# R302X.net
KiCad netlist of a schematic drawn in EAGLE
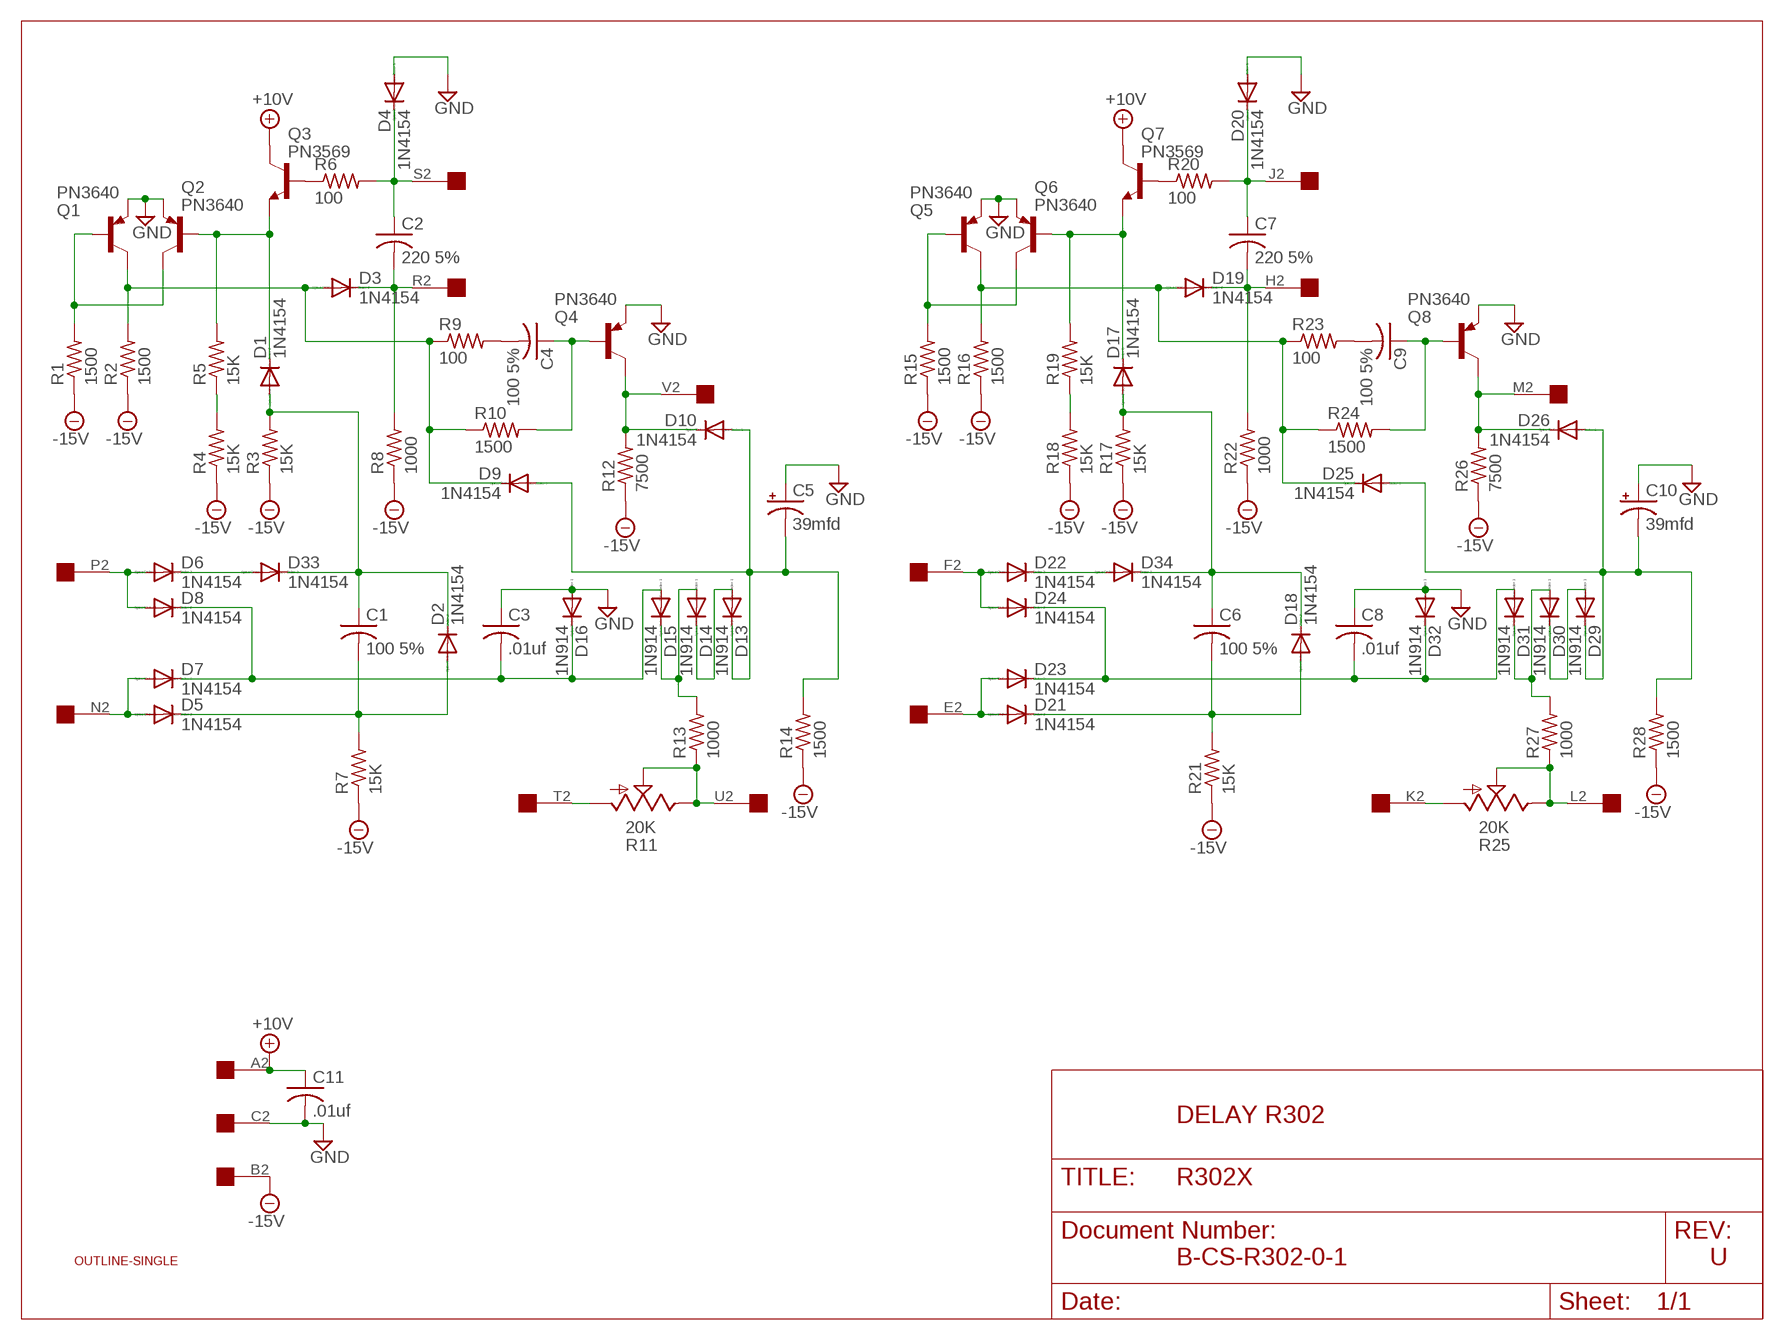
[diagram p0: schematic, sheet 1]

(export (version "E")
  (design (tool "Eeschema 10.0.6"))
  (components
    (comp (ref "C1")
      (value "100 5%")
      (footprint "eagle-import:C050-025X075")
      (libsource (lib "eagle-import") (part "C-US050-025X075"))
    )
    (comp (ref "C2")
      (value "220 5%")
      (footprint "eagle-import:C050-025X075")
      (libsource (lib "eagle-import") (part "C-US050-025X075"))
    )
    (comp (ref "C3")
      (value ".01uf")
      (footprint "eagle-import:C050-025X075")
      (libsource (lib "eagle-import") (part "C-US050-025X075"))
    )
    (comp (ref "C4")
      (value "100 5%")
      (footprint "eagle-import:C050-025X075")
      (libsource (lib "eagle-import") (part "C-US050-025X075"))
    )
    (comp (ref "C5")
      (value "39mfd")
      (footprint "eagle-import:E15-5")
      (libsource (lib "eagle-import") (part "CPOL-USE15-5AXIAL"))
    )
    (comp (ref "C6")
      (value "100 5%")
      (footprint "eagle-import:C050-025X075")
      (libsource (lib "eagle-import") (part "C-US050-025X075"))
    )
    (comp (ref "C7")
      (value "220 5%")
      (footprint "eagle-import:C050-025X075")
      (libsource (lib "eagle-import") (part "C-US050-025X075"))
    )
    (comp (ref "C8")
      (value ".01uf")
      (footprint "eagle-import:C050-025X075")
      (libsource (lib "eagle-import") (part "C-US050-025X075"))
    )
    (comp (ref "C9")
      (value "100 5%")
      (footprint "eagle-import:C050-025X075")
      (libsource (lib "eagle-import") (part "C-US050-025X075"))
    )
    (comp (ref "C10")
      (value "39mfd")
      (footprint "eagle-import:E15-5")
      (libsource (lib "eagle-import") (part "CPOL-USE15-5AXIAL"))
    )
    (comp (ref "C11")
      (value ".01uf")
      (footprint "eagle-import:C050-025X075")
      (libsource (lib "eagle-import") (part "C-US050-025X075"))
    )
    (comp (ref "D1")
      (value "1N4154")
      (footprint "eagle-import:DO35-10")
      (libsource (lib "eagle-import") (part "1N4148DO35-10"))
    )
    (comp (ref "D2")
      (value "1N4154")
      (footprint "eagle-import:DO35-10")
      (libsource (lib "eagle-import") (part "1N4148DO35-10"))
    )
    (comp (ref "D3")
      (value "1N4154")
      (footprint "eagle-import:DO35-10")
      (libsource (lib "eagle-import") (part "1N4148DO35-10"))
    )
    (comp (ref "D4")
      (value "1N4154")
      (footprint "eagle-import:DO35-10")
      (libsource (lib "eagle-import") (part "1N4148DO35-10"))
    )
    (comp (ref "D5")
      (value "1N4154")
      (footprint "eagle-import:DO35-10")
      (libsource (lib "eagle-import") (part "1N4148DO35-10"))
    )
    (comp (ref "D6")
      (value "1N4154")
      (footprint "eagle-import:DO35-10")
      (libsource (lib "eagle-import") (part "1N4148DO35-10"))
    )
    (comp (ref "D7")
      (value "1N4154")
      (footprint "eagle-import:DO35-10")
      (libsource (lib "eagle-import") (part "1N4148DO35-10"))
    )
    (comp (ref "D8")
      (value "1N4154")
      (footprint "eagle-import:DO35-10")
      (libsource (lib "eagle-import") (part "1N4148DO35-10"))
    )
    (comp (ref "D9")
      (value "1N4154")
      (footprint "eagle-import:DO35-10")
      (libsource (lib "eagle-import") (part "1N4148DO35-10"))
    )
    (comp (ref "D10")
      (value "1N4154")
      (footprint "eagle-import:DO35-10")
      (libsource (lib "eagle-import") (part "1N4148DO35-10"))
    )
    (comp (ref "D13")
      (value "1N914")
      (footprint "eagle-import:DO35-10")
      (libsource (lib "eagle-import") (part "1N4148DO35-10"))
    )
    (comp (ref "D14")
      (value "1N914")
      (footprint "eagle-import:DO35-10")
      (libsource (lib "eagle-import") (part "1N4148DO35-10"))
    )
    (comp (ref "D15")
      (value "1N914")
      (footprint "eagle-import:DO35-10")
      (libsource (lib "eagle-import") (part "1N4148DO35-10"))
    )
    (comp (ref "D16")
      (value "1N914")
      (footprint "eagle-import:DO35-10")
      (libsource (lib "eagle-import") (part "1N4148DO35-10"))
    )
    (comp (ref "D17")
      (value "1N4154")
      (footprint "eagle-import:DO35-10")
      (libsource (lib "eagle-import") (part "1N4148DO35-10"))
    )
    (comp (ref "D18")
      (value "1N4154")
      (footprint "eagle-import:DO35-10")
      (libsource (lib "eagle-import") (part "1N4148DO35-10"))
    )
    (comp (ref "D19")
      (value "1N4154")
      (footprint "eagle-import:DO35-10")
      (libsource (lib "eagle-import") (part "1N4148DO35-10"))
    )
    (comp (ref "D20")
      (value "1N4154")
      (footprint "eagle-import:DO35-10")
      (libsource (lib "eagle-import") (part "1N4148DO35-10"))
    )
    (comp (ref "D21")
      (value "1N4154")
      (footprint "eagle-import:DO35-10")
      (libsource (lib "eagle-import") (part "1N4148DO35-10"))
    )
    (comp (ref "D22")
      (value "1N4154")
      (footprint "eagle-import:DO35-10")
      (libsource (lib "eagle-import") (part "1N4148DO35-10"))
    )
    (comp (ref "D23")
      (value "1N4154")
      (footprint "eagle-import:DO35-10")
      (libsource (lib "eagle-import") (part "1N4148DO35-10"))
    )
    (comp (ref "D24")
      (value "1N4154")
      (footprint "eagle-import:DO35-10")
      (libsource (lib "eagle-import") (part "1N4148DO35-10"))
    )
    (comp (ref "D25")
      (value "1N4154")
      (footprint "eagle-import:DO35-10")
      (libsource (lib "eagle-import") (part "1N4148DO35-10"))
    )
    (comp (ref "D26")
      (value "1N4154")
      (footprint "eagle-import:DO35-10")
      (libsource (lib "eagle-import") (part "1N4148DO35-10"))
    )
    (comp (ref "D29")
      (value "1N914")
      (footprint "eagle-import:DO35-10")
      (libsource (lib "eagle-import") (part "1N4148DO35-10"))
    )
    (comp (ref "D30")
      (value "1N914")
      (footprint "eagle-import:DO35-10")
      (libsource (lib "eagle-import") (part "1N4148DO35-10"))
    )
    (comp (ref "D31")
      (value "1N914")
      (footprint "eagle-import:DO35-10")
      (libsource (lib "eagle-import") (part "1N4148DO35-10"))
    )
    (comp (ref "D32")
      (value "1N914")
      (footprint "eagle-import:DO35-10")
      (libsource (lib "eagle-import") (part "1N4148DO35-10"))
    )
    (comp (ref "D33")
      (value "1N4154")
      (footprint "eagle-import:DO35-10")
      (libsource (lib "eagle-import") (part "1N4148DO35-10"))
    )
    (comp (ref "D34")
      (value "1N4154")
      (footprint "eagle-import:DO35-10")
      (libsource (lib "eagle-import") (part "1N4148DO35-10"))
    )
    (comp (ref "Q1")
      (value "PN3640")
      (footprint "eagle-import:TO39")
      (libsource (lib "eagle-import") (part "2N3637"))
    )
    (comp (ref "Q2")
      (value "PN3640")
      (footprint "eagle-import:TO39")
      (libsource (lib "eagle-import") (part "2N3637"))
    )
    (comp (ref "Q3")
      (value "PN3569")
      (footprint "eagle-import:TO39")
      (libsource (lib "eagle-import") (part "-NPN-TO39-EBC2N3019"))
    )
    (comp (ref "Q4")
      (value "PN3640")
      (footprint "eagle-import:TO39")
      (libsource (lib "eagle-import") (part "2N3637"))
    )
    (comp (ref "Q5")
      (value "PN3640")
      (footprint "eagle-import:TO39")
      (libsource (lib "eagle-import") (part "2N3637"))
    )
    (comp (ref "Q6")
      (value "PN3640")
      (footprint "eagle-import:TO39")
      (libsource (lib "eagle-import") (part "2N3637"))
    )
    (comp (ref "Q7")
      (value "PN3569")
      (footprint "eagle-import:TO39")
      (libsource (lib "eagle-import") (part "-NPN-TO39-EBC2N3019"))
    )
    (comp (ref "Q8")
      (value "PN3640")
      (footprint "eagle-import:TO39")
      (libsource (lib "eagle-import") (part "2N3637"))
    )
    (comp (ref "R1")
      (value "1500")
      (footprint "eagle-import:0207_10")
      (libsource (lib "eagle-import") (part "R-US_0207/10"))
    )
    (comp (ref "R2")
      (value "1500")
      (footprint "eagle-import:0207_10")
      (libsource (lib "eagle-import") (part "R-US_0207/10"))
    )
    (comp (ref "R3")
      (value "15K")
      (footprint "eagle-import:0207_10")
      (libsource (lib "eagle-import") (part "R-US_0207/10"))
    )
    (comp (ref "R4")
      (value "15K")
      (footprint "eagle-import:0207_10")
      (libsource (lib "eagle-import") (part "R-US_0207/10"))
    )
    (comp (ref "R5")
      (value "15K")
      (footprint "eagle-import:0207_10")
      (libsource (lib "eagle-import") (part "R-US_0207/10"))
    )
    (comp (ref "R6")
      (value "100")
      (footprint "eagle-import:0207_10")
      (libsource (lib "eagle-import") (part "R-US_0207/10"))
    )
    (comp (ref "R7")
      (value "15K")
      (footprint "eagle-import:0207_10")
      (libsource (lib "eagle-import") (part "R-US_0207/10"))
    )
    (comp (ref "R8")
      (value "1000")
      (footprint "eagle-import:0207_10")
      (libsource (lib "eagle-import") (part "R-US_0207/10"))
    )
    (comp (ref "R9")
      (value "100")
      (footprint "eagle-import:0207_10")
      (libsource (lib "eagle-import") (part "R-US_0207/10"))
    )
    (comp (ref "R10")
      (value "1500")
      (footprint "eagle-import:0207_10")
      (libsource (lib "eagle-import") (part "R-US_0207/10"))
    )
    (comp (ref "R11")
      (value "20K")
      (footprint "eagle-import:SP19L")
      (libsource (lib "eagle-import") (part "TRIM_US-S43P"))
    )
    (comp (ref "R12")
      (value "7500")
      (footprint "eagle-import:0207_10")
      (libsource (lib "eagle-import") (part "R-US_0207/10"))
    )
    (comp (ref "R13")
      (value "1000")
      (footprint "eagle-import:0207_10")
      (libsource (lib "eagle-import") (part "R-US_0207/10"))
    )
    (comp (ref "R14")
      (value "1500")
      (footprint "eagle-import:0207_10")
      (libsource (lib "eagle-import") (part "R-US_0207/10"))
    )
    (comp (ref "R15")
      (value "1500")
      (footprint "eagle-import:0207_10")
      (libsource (lib "eagle-import") (part "R-US_0207/10"))
    )
    (comp (ref "R16")
      (value "1500")
      (footprint "eagle-import:0207_10")
      (libsource (lib "eagle-import") (part "R-US_0207/10"))
    )
    (comp (ref "R17")
      (value "15K")
      (footprint "eagle-import:0207_10")
      (libsource (lib "eagle-import") (part "R-US_0207/10"))
    )
    (comp (ref "R18")
      (value "15K")
      (footprint "eagle-import:0207_10")
      (libsource (lib "eagle-import") (part "R-US_0207/10"))
    )
    (comp (ref "R19")
      (value "15K")
      (footprint "eagle-import:0207_10")
      (libsource (lib "eagle-import") (part "R-US_0207/10"))
    )
    (comp (ref "R20")
      (value "100")
      (footprint "eagle-import:0207_10")
      (libsource (lib "eagle-import") (part "R-US_0207/10"))
    )
    (comp (ref "R21")
      (value "15K")
      (footprint "eagle-import:0207_10")
      (libsource (lib "eagle-import") (part "R-US_0207/10"))
    )
    (comp (ref "R22")
      (value "1000")
      (footprint "eagle-import:0207_10")
      (libsource (lib "eagle-import") (part "R-US_0207/10"))
    )
    (comp (ref "R23")
      (value "100")
      (footprint "eagle-import:0207_10")
      (libsource (lib "eagle-import") (part "R-US_0207/10"))
    )
    (comp (ref "R24")
      (value "1500")
      (footprint "eagle-import:0207_10")
      (libsource (lib "eagle-import") (part "R-US_0207/10"))
    )
    (comp (ref "R25")
      (value "20K")
      (footprint "eagle-import:SP19L")
      (libsource (lib "eagle-import") (part "TRIM_US-S43P"))
    )
    (comp (ref "R26")
      (value "7500")
      (footprint "eagle-import:0207_10")
      (libsource (lib "eagle-import") (part "R-US_0207/10"))
    )
    (comp (ref "R27")
      (value "1000")
      (footprint "eagle-import:0207_10")
      (libsource (lib "eagle-import") (part "R-US_0207/10"))
    )
    (comp (ref "R28")
      (value "1500")
      (footprint "eagle-import:0207_10")
      (libsource (lib "eagle-import") (part "R-US_0207/10"))
    )
    (comp (ref "U$1")
      (value "OUTLINE-SINGLE")
      (footprint "eagle-import:SINGLE")
      (libsource (lib "eagle-import") (part "OUTLINE-SINGLE"))
    )
    (comp (ref "U$2")
      (value "EDGE-1")
      (footprint "eagle-import:EDGE-CON1")
      (libsource (lib "eagle-import") (part "EDGE-1"))
    )
  )
  (nets
    (net (code "1") (name "+10V") (class "Default")
      (node (ref "C11") (pin "1") (pinfunction "1_1") (pintype "passive"))
      (node (ref "Q3") (pin "3") (pinfunction "C_3") (pintype "passive"))
      (node (ref "Q7") (pin "3") (pinfunction "C_3") (pintype "passive"))
      (node (ref "U$2") (pin "A2") (pinfunction "1_A2") (pintype "bidirectional"))
    )
    (net (code "2") (name "-15V") (class "Default")
      (node (ref "R1") (pin "1") (pinfunction "1_1") (pintype "passive"))
      (node (ref "R12") (pin "1") (pinfunction "1_1") (pintype "passive"))
      (node (ref "R14") (pin "1") (pinfunction "1_1") (pintype "passive"))
      (node (ref "R15") (pin "1") (pinfunction "1_1") (pintype "passive"))
      (node (ref "R16") (pin "1") (pinfunction "1_1") (pintype "passive"))
      (node (ref "R17") (pin "1") (pinfunction "1_1") (pintype "passive"))
      (node (ref "R18") (pin "1") (pinfunction "1_1") (pintype "passive"))
      (node (ref "R2") (pin "1") (pinfunction "1_1") (pintype "passive"))
      (node (ref "R21") (pin "1") (pinfunction "1_1") (pintype "passive"))
      (node (ref "R22") (pin "1") (pinfunction "1_1") (pintype "passive"))
      (node (ref "R26") (pin "1") (pinfunction "1_1") (pintype "passive"))
      (node (ref "R28") (pin "1") (pinfunction "1_1") (pintype "passive"))
      (node (ref "R3") (pin "1") (pinfunction "1_1") (pintype "passive"))
      (node (ref "R4") (pin "1") (pinfunction "1_1") (pintype "passive"))
      (node (ref "R7") (pin "1") (pinfunction "1_1") (pintype "passive"))
      (node (ref "R8") (pin "1") (pinfunction "1_1") (pintype "passive"))
      (node (ref "U$2") (pin "B2") (pinfunction "1_B2") (pintype "bidirectional"))
    )
    (net (code "3") (name "GND") (class "Default")
      (node (ref "C10") (pin "+") (pinfunction "+_+") (pintype "passive"))
      (node (ref "C11") (pin "2") (pinfunction "2_2") (pintype "passive"))
      (node (ref "C3") (pin "1") (pinfunction "1_1") (pintype "passive"))
      (node (ref "C5") (pin "+") (pinfunction "+_+") (pintype "passive"))
      (node (ref "C8") (pin "1") (pinfunction "1_1") (pintype "passive"))
      (node (ref "D16") (pin "A") (pinfunction "A_A") (pintype "passive"))
      (node (ref "D20") (pin "A") (pinfunction "A_A") (pintype "passive"))
      (node (ref "D32") (pin "A") (pinfunction "A_A") (pintype "passive"))
      (node (ref "D4") (pin "A") (pinfunction "A_A") (pintype "passive"))
      (node (ref "Q1") (pin "1") (pinfunction "E_1") (pintype "passive"))
      (node (ref "Q2") (pin "1") (pinfunction "E_1") (pintype "passive"))
      (node (ref "Q4") (pin "1") (pinfunction "E_1") (pintype "passive"))
      (node (ref "Q5") (pin "1") (pinfunction "E_1") (pintype "passive"))
      (node (ref "Q6") (pin "1") (pinfunction "E_1") (pintype "passive"))
      (node (ref "Q8") (pin "1") (pinfunction "E_1") (pintype "passive"))
      (node (ref "U$2") (pin "C2") (pinfunction "1_C2") (pintype "bidirectional"))
    )
    (net (code "4") (name "Net-(C1-Pad1)") (class "Default")
      (node (ref "C1") (pin "1") (pinfunction "1_1") (pintype "passive"))
      (node (ref "D1") (pin "A") (pinfunction "A_A") (pintype "passive"))
      (node (ref "D2") (pin "C") (pinfunction "C_C") (pintype "passive"))
      (node (ref "D33") (pin "C") (pinfunction "C_C") (pintype "passive"))
      (node (ref "R3") (pin "2") (pinfunction "2_2") (pintype "passive"))
    )
    (net (code "5") (name "Net-(C1-Pad2)") (class "Default")
      (node (ref "C1") (pin "2") (pinfunction "2_2") (pintype "passive"))
      (node (ref "D2") (pin "A") (pinfunction "A_A") (pintype "passive"))
      (node (ref "D5") (pin "C") (pinfunction "C_C") (pintype "passive"))
      (node (ref "R7") (pin "2") (pinfunction "2_2") (pintype "passive"))
    )
    (net (code "6") (name "Net-(C3-Pad2)") (class "Default")
      (node (ref "C3") (pin "2") (pinfunction "2_2") (pintype "passive"))
      (node (ref "D15") (pin "A") (pinfunction "A_A") (pintype "passive"))
      (node (ref "D16") (pin "C") (pinfunction "C_C") (pintype "passive"))
      (node (ref "D7") (pin "C") (pinfunction "C_C") (pintype "passive"))
      (node (ref "D8") (pin "C") (pinfunction "C_C") (pintype "passive"))
    )
    (net (code "7") (name "Net-(C4-Pad2)") (class "Default")
      (node (ref "C4") (pin "2") (pinfunction "2_2") (pintype "passive"))
      (node (ref "R9") (pin "2") (pinfunction "2_2") (pintype "passive"))
    )
    (net (code "8") (name "Net-(C5-Pad-)") (class "Default")
      (node (ref "C5") (pin "-") (pinfunction "-_-") (pintype "passive"))
      (node (ref "D10") (pin "A") (pinfunction "A_A") (pintype "passive"))
      (node (ref "D13") (pin "C") (pinfunction "C_C") (pintype "passive"))
      (node (ref "D9") (pin "A") (pinfunction "A_A") (pintype "passive"))
      (node (ref "R14") (pin "2") (pinfunction "2_2") (pintype "passive"))
    )
    (net (code "9") (name "Net-(C6-Pad1)") (class "Default")
      (node (ref "C6") (pin "1") (pinfunction "1_1") (pintype "passive"))
      (node (ref "D17") (pin "A") (pinfunction "A_A") (pintype "passive"))
      (node (ref "D18") (pin "C") (pinfunction "C_C") (pintype "passive"))
      (node (ref "D34") (pin "C") (pinfunction "C_C") (pintype "passive"))
      (node (ref "R17") (pin "2") (pinfunction "2_2") (pintype "passive"))
    )
    (net (code "10") (name "Net-(C6-Pad2)") (class "Default")
      (node (ref "C6") (pin "2") (pinfunction "2_2") (pintype "passive"))
      (node (ref "D18") (pin "A") (pinfunction "A_A") (pintype "passive"))
      (node (ref "D21") (pin "C") (pinfunction "C_C") (pintype "passive"))
      (node (ref "R21") (pin "2") (pinfunction "2_2") (pintype "passive"))
    )
    (net (code "11") (name "Net-(C8-Pad2)") (class "Default")
      (node (ref "C8") (pin "2") (pinfunction "2_2") (pintype "passive"))
      (node (ref "D23") (pin "C") (pinfunction "C_C") (pintype "passive"))
      (node (ref "D24") (pin "C") (pinfunction "C_C") (pintype "passive"))
      (node (ref "D31") (pin "A") (pinfunction "A_A") (pintype "passive"))
      (node (ref "D32") (pin "C") (pinfunction "C_C") (pintype "passive"))
    )
    (net (code "12") (name "Net-(C9-Pad2)") (class "Default")
      (node (ref "C9") (pin "2") (pinfunction "2_2") (pintype "passive"))
      (node (ref "R23") (pin "2") (pinfunction "2_2") (pintype "passive"))
    )
    (net (code "13") (name "Net-(C10-Pad-)") (class "Default")
      (node (ref "C10") (pin "-") (pinfunction "-_-") (pintype "passive"))
      (node (ref "D25") (pin "A") (pinfunction "A_A") (pintype "passive"))
      (node (ref "D26") (pin "A") (pinfunction "A_A") (pintype "passive"))
      (node (ref "D29") (pin "C") (pinfunction "C_C") (pintype "passive"))
      (node (ref "R28") (pin "2") (pinfunction "2_2") (pintype "passive"))
    )
    (net (code "14") (name "Net-(D13-PadA)") (class "Default")
      (node (ref "D13") (pin "A") (pinfunction "A_A") (pintype "passive"))
      (node (ref "D14") (pin "C") (pinfunction "C_C") (pintype "passive"))
    )
    (net (code "15") (name "Net-(D14-PadA)") (class "Default")
      (node (ref "D14") (pin "A") (pinfunction "A_A") (pintype "passive"))
      (node (ref "D15") (pin "C") (pinfunction "C_C") (pintype "passive"))
      (node (ref "R13") (pin "2") (pinfunction "2_2") (pintype "passive"))
    )
    (net (code "16") (name "Net-(D22-PadC)") (class "Default")
      (node (ref "D22") (pin "C") (pinfunction "C_C") (pintype "passive"))
      (node (ref "D34") (pin "A") (pinfunction "A_A") (pintype "passive"))
    )
    (net (code "17") (name "Net-(D29-PadA)") (class "Default")
      (node (ref "D29") (pin "A") (pinfunction "A_A") (pintype "passive"))
      (node (ref "D30") (pin "C") (pinfunction "C_C") (pintype "passive"))
    )
    (net (code "18") (name "Net-(D30-PadA)") (class "Default")
      (node (ref "D30") (pin "A") (pinfunction "A_A") (pintype "passive"))
      (node (ref "D31") (pin "C") (pinfunction "C_C") (pintype "passive"))
      (node (ref "R27") (pin "2") (pinfunction "2_2") (pintype "passive"))
    )
    (net (code "19") (name "Net-(D33-PadA)") (class "Default")
      (node (ref "D33") (pin "A") (pinfunction "A_A") (pintype "passive"))
      (node (ref "D6") (pin "C") (pinfunction "C_C") (pintype "passive"))
    )
    (net (code "20") (name "Net-(Q1-B)") (class "Default")
      (node (ref "Q1") (pin "2") (pinfunction "B_2") (pintype "passive"))
      (node (ref "Q2") (pin "3") (pinfunction "C_3") (pintype "passive"))
      (node (ref "R1") (pin "2") (pinfunction "2_2") (pintype "passive"))
    )
    (net (code "21") (name "Net-(Q1-C)") (class "Default")
      (node (ref "D3") (pin "A") (pinfunction "A_A") (pintype "passive"))
      (node (ref "D9") (pin "C") (pinfunction "C_C") (pintype "passive"))
      (node (ref "Q1") (pin "3") (pinfunction "C_3") (pintype "passive"))
      (node (ref "R10") (pin "1") (pinfunction "1_1") (pintype "passive"))
      (node (ref "R2") (pin "2") (pinfunction "2_2") (pintype "passive"))
      (node (ref "R9") (pin "1") (pinfunction "1_1") (pintype "passive"))
    )
    (net (code "22") (name "Net-(Q2-B)") (class "Default")
      (node (ref "D1") (pin "C") (pinfunction "C_C") (pintype "passive"))
      (node (ref "Q2") (pin "2") (pinfunction "B_2") (pintype "passive"))
      (node (ref "Q3") (pin "1") (pinfunction "E_1") (pintype "passive"))
      (node (ref "R5") (pin "2") (pinfunction "2_2") (pintype "passive"))
    )
    (net (code "23") (name "Net-(Q3-B)") (class "Default")
      (node (ref "Q3") (pin "2") (pinfunction "B_2") (pintype "passive"))
      (node (ref "R6") (pin "1") (pinfunction "1_1") (pintype "passive"))
    )
    (net (code "24") (name "Net-(Q4-B)") (class "Default")
      (node (ref "C4") (pin "1") (pinfunction "1_1") (pintype "passive"))
      (node (ref "Q4") (pin "2") (pinfunction "B_2") (pintype "passive"))
      (node (ref "R10") (pin "2") (pinfunction "2_2") (pintype "passive"))
    )
    (net (code "25") (name "Net-(Q4-C)") (class "Default")
      (node (ref "D10") (pin "C") (pinfunction "C_C") (pintype "passive"))
      (node (ref "Q4") (pin "3") (pinfunction "C_3") (pintype "passive"))
      (node (ref "R12") (pin "2") (pinfunction "2_2") (pintype "passive"))
      (node (ref "U$2") (pin "V2") (pinfunction "1_V2") (pintype "bidirectional"))
    )
    (net (code "26") (name "Net-(Q5-B)") (class "Default")
      (node (ref "Q5") (pin "2") (pinfunction "B_2") (pintype "passive"))
      (node (ref "Q6") (pin "3") (pinfunction "C_3") (pintype "passive"))
      (node (ref "R15") (pin "2") (pinfunction "2_2") (pintype "passive"))
    )
    (net (code "27") (name "Net-(Q5-C)") (class "Default")
      (node (ref "D19") (pin "A") (pinfunction "A_A") (pintype "passive"))
      (node (ref "D25") (pin "C") (pinfunction "C_C") (pintype "passive"))
      (node (ref "Q5") (pin "3") (pinfunction "C_3") (pintype "passive"))
      (node (ref "R16") (pin "2") (pinfunction "2_2") (pintype "passive"))
      (node (ref "R23") (pin "1") (pinfunction "1_1") (pintype "passive"))
      (node (ref "R24") (pin "1") (pinfunction "1_1") (pintype "passive"))
    )
    (net (code "28") (name "Net-(Q6-B)") (class "Default")
      (node (ref "D17") (pin "C") (pinfunction "C_C") (pintype "passive"))
      (node (ref "Q6") (pin "2") (pinfunction "B_2") (pintype "passive"))
      (node (ref "Q7") (pin "1") (pinfunction "E_1") (pintype "passive"))
      (node (ref "R19") (pin "2") (pinfunction "2_2") (pintype "passive"))
    )
    (net (code "29") (name "Net-(Q7-B)") (class "Default")
      (node (ref "Q7") (pin "2") (pinfunction "B_2") (pintype "passive"))
      (node (ref "R20") (pin "1") (pinfunction "1_1") (pintype "passive"))
    )
    (net (code "30") (name "Net-(Q8-B)") (class "Default")
      (node (ref "C9") (pin "1") (pinfunction "1_1") (pintype "passive"))
      (node (ref "Q8") (pin "2") (pinfunction "B_2") (pintype "passive"))
      (node (ref "R24") (pin "2") (pinfunction "2_2") (pintype "passive"))
    )
    (net (code "31") (name "Net-(Q8-C)") (class "Default")
      (node (ref "D26") (pin "C") (pinfunction "C_C") (pintype "passive"))
      (node (ref "Q8") (pin "3") (pinfunction "C_3") (pintype "passive"))
      (node (ref "R26") (pin "2") (pinfunction "2_2") (pintype "passive"))
      (node (ref "U$2") (pin "M2") (pinfunction "1_M2") (pintype "bidirectional"))
    )
    (net (code "32") (name "Net-(R4-Pad2)") (class "Default")
      (node (ref "R4") (pin "2") (pinfunction "2_2") (pintype "passive"))
      (node (ref "R5") (pin "1") (pinfunction "1_1") (pintype "passive"))
    )
    (net (code "33") (name "Net-(R18-Pad2)") (class "Default")
      (node (ref "R18") (pin "2") (pinfunction "2_2") (pintype "passive"))
      (node (ref "R19") (pin "1") (pinfunction "1_1") (pintype "passive"))
    )
    (net (code "34") (name "Net-(U$2E-1)") (class "Default")
      (node (ref "D21") (pin "A") (pinfunction "A_A") (pintype "passive"))
      (node (ref "D23") (pin "A") (pinfunction "A_A") (pintype "passive"))
      (node (ref "U$2") (pin "E2") (pinfunction "1_E2") (pintype "bidirectional"))
    )
    (net (code "35") (name "Net-(U$2F-1)") (class "Default")
      (node (ref "D22") (pin "A") (pinfunction "A_A") (pintype "passive"))
      (node (ref "D24") (pin "A") (pinfunction "A_A") (pintype "passive"))
      (node (ref "U$2") (pin "F2") (pinfunction "1_F2") (pintype "bidirectional"))
    )
    (net (code "36") (name "Net-(U$2G-1)") (class "Default")
      (node (ref "C7") (pin "2") (pinfunction "2_2") (pintype "passive"))
      (node (ref "D19") (pin "C") (pinfunction "C_C") (pintype "passive"))
      (node (ref "R22") (pin "2") (pinfunction "2_2") (pintype "passive"))
      (node (ref "U$2") (pin "H2") (pinfunction "1_H2") (pintype "bidirectional"))
    )
    (net (code "37") (name "Net-(U$2H-1)") (class "Default")
      (node (ref "C7") (pin "1") (pinfunction "1_1") (pintype "passive"))
      (node (ref "D20") (pin "C") (pinfunction "C_C") (pintype "passive"))
      (node (ref "R20") (pin "2") (pinfunction "2_2") (pintype "passive"))
      (node (ref "U$2") (pin "J2") (pinfunction "1_J2") (pintype "bidirectional"))
    )
    (net (code "38") (name "Net-(U$2I-1)") (class "Default")
      (node (ref "R25") (pin "A") (pinfunction "A_A") (pintype "passive"))
      (node (ref "U$2") (pin "K2") (pinfunction "1_K2") (pintype "bidirectional"))
    )
    (net (code "39") (name "Net-(U$2J-1)") (class "Default")
      (node (ref "R25") (pin "E") (pinfunction "E_E") (pintype "passive"))
      (node (ref "R25") (pin "S") (pinfunction "S_S") (pintype "passive"))
      (node (ref "R27") (pin "1") (pinfunction "1_1") (pintype "passive"))
      (node (ref "U$2") (pin "L2") (pinfunction "1_L2") (pintype "bidirectional"))
    )
    (net (code "40") (name "Net-(U$2L-1)") (class "Default")
      (node (ref "D5") (pin "A") (pinfunction "A_A") (pintype "passive"))
      (node (ref "D7") (pin "A") (pinfunction "A_A") (pintype "passive"))
      (node (ref "U$2") (pin "N2") (pinfunction "1_N2") (pintype "bidirectional"))
    )
    (net (code "41") (name "Net-(U$2M-1)") (class "Default")
      (node (ref "D6") (pin "A") (pinfunction "A_A") (pintype "passive"))
      (node (ref "D8") (pin "A") (pinfunction "A_A") (pintype "passive"))
      (node (ref "U$2") (pin "P2") (pinfunction "1_P2") (pintype "bidirectional"))
    )
    (net (code "42") (name "Net-(U$2N-1)") (class "Default")
      (node (ref "C2") (pin "2") (pinfunction "2_2") (pintype "passive"))
      (node (ref "D3") (pin "C") (pinfunction "C_C") (pintype "passive"))
      (node (ref "R8") (pin "2") (pinfunction "2_2") (pintype "passive"))
      (node (ref "U$2") (pin "R2") (pinfunction "1_R2") (pintype "bidirectional"))
    )
    (net (code "43") (name "Net-(U$2O-1)") (class "Default")
      (node (ref "C2") (pin "1") (pinfunction "1_1") (pintype "passive"))
      (node (ref "D4") (pin "C") (pinfunction "C_C") (pintype "passive"))
      (node (ref "R6") (pin "2") (pinfunction "2_2") (pintype "passive"))
      (node (ref "U$2") (pin "S2") (pinfunction "1_S2") (pintype "bidirectional"))
    )
    (net (code "44") (name "Net-(U$2P-1)") (class "Default")
      (node (ref "R11") (pin "A") (pinfunction "A_A") (pintype "passive"))
      (node (ref "U$2") (pin "T2") (pinfunction "1_T2") (pintype "bidirectional"))
    )
    (net (code "45") (name "Net-(U$2Q-1)") (class "Default")
      (node (ref "R11") (pin "E") (pinfunction "E_E") (pintype "passive"))
      (node (ref "R11") (pin "S") (pinfunction "S_S") (pintype "passive"))
      (node (ref "R13") (pin "1") (pinfunction "1_1") (pintype "passive"))
      (node (ref "U$2") (pin "U2") (pinfunction "1_U2") (pintype "bidirectional"))
    )
  )
)
